# Input_channel.net
KiCad netlist of a schematic drawn in Altium Designer
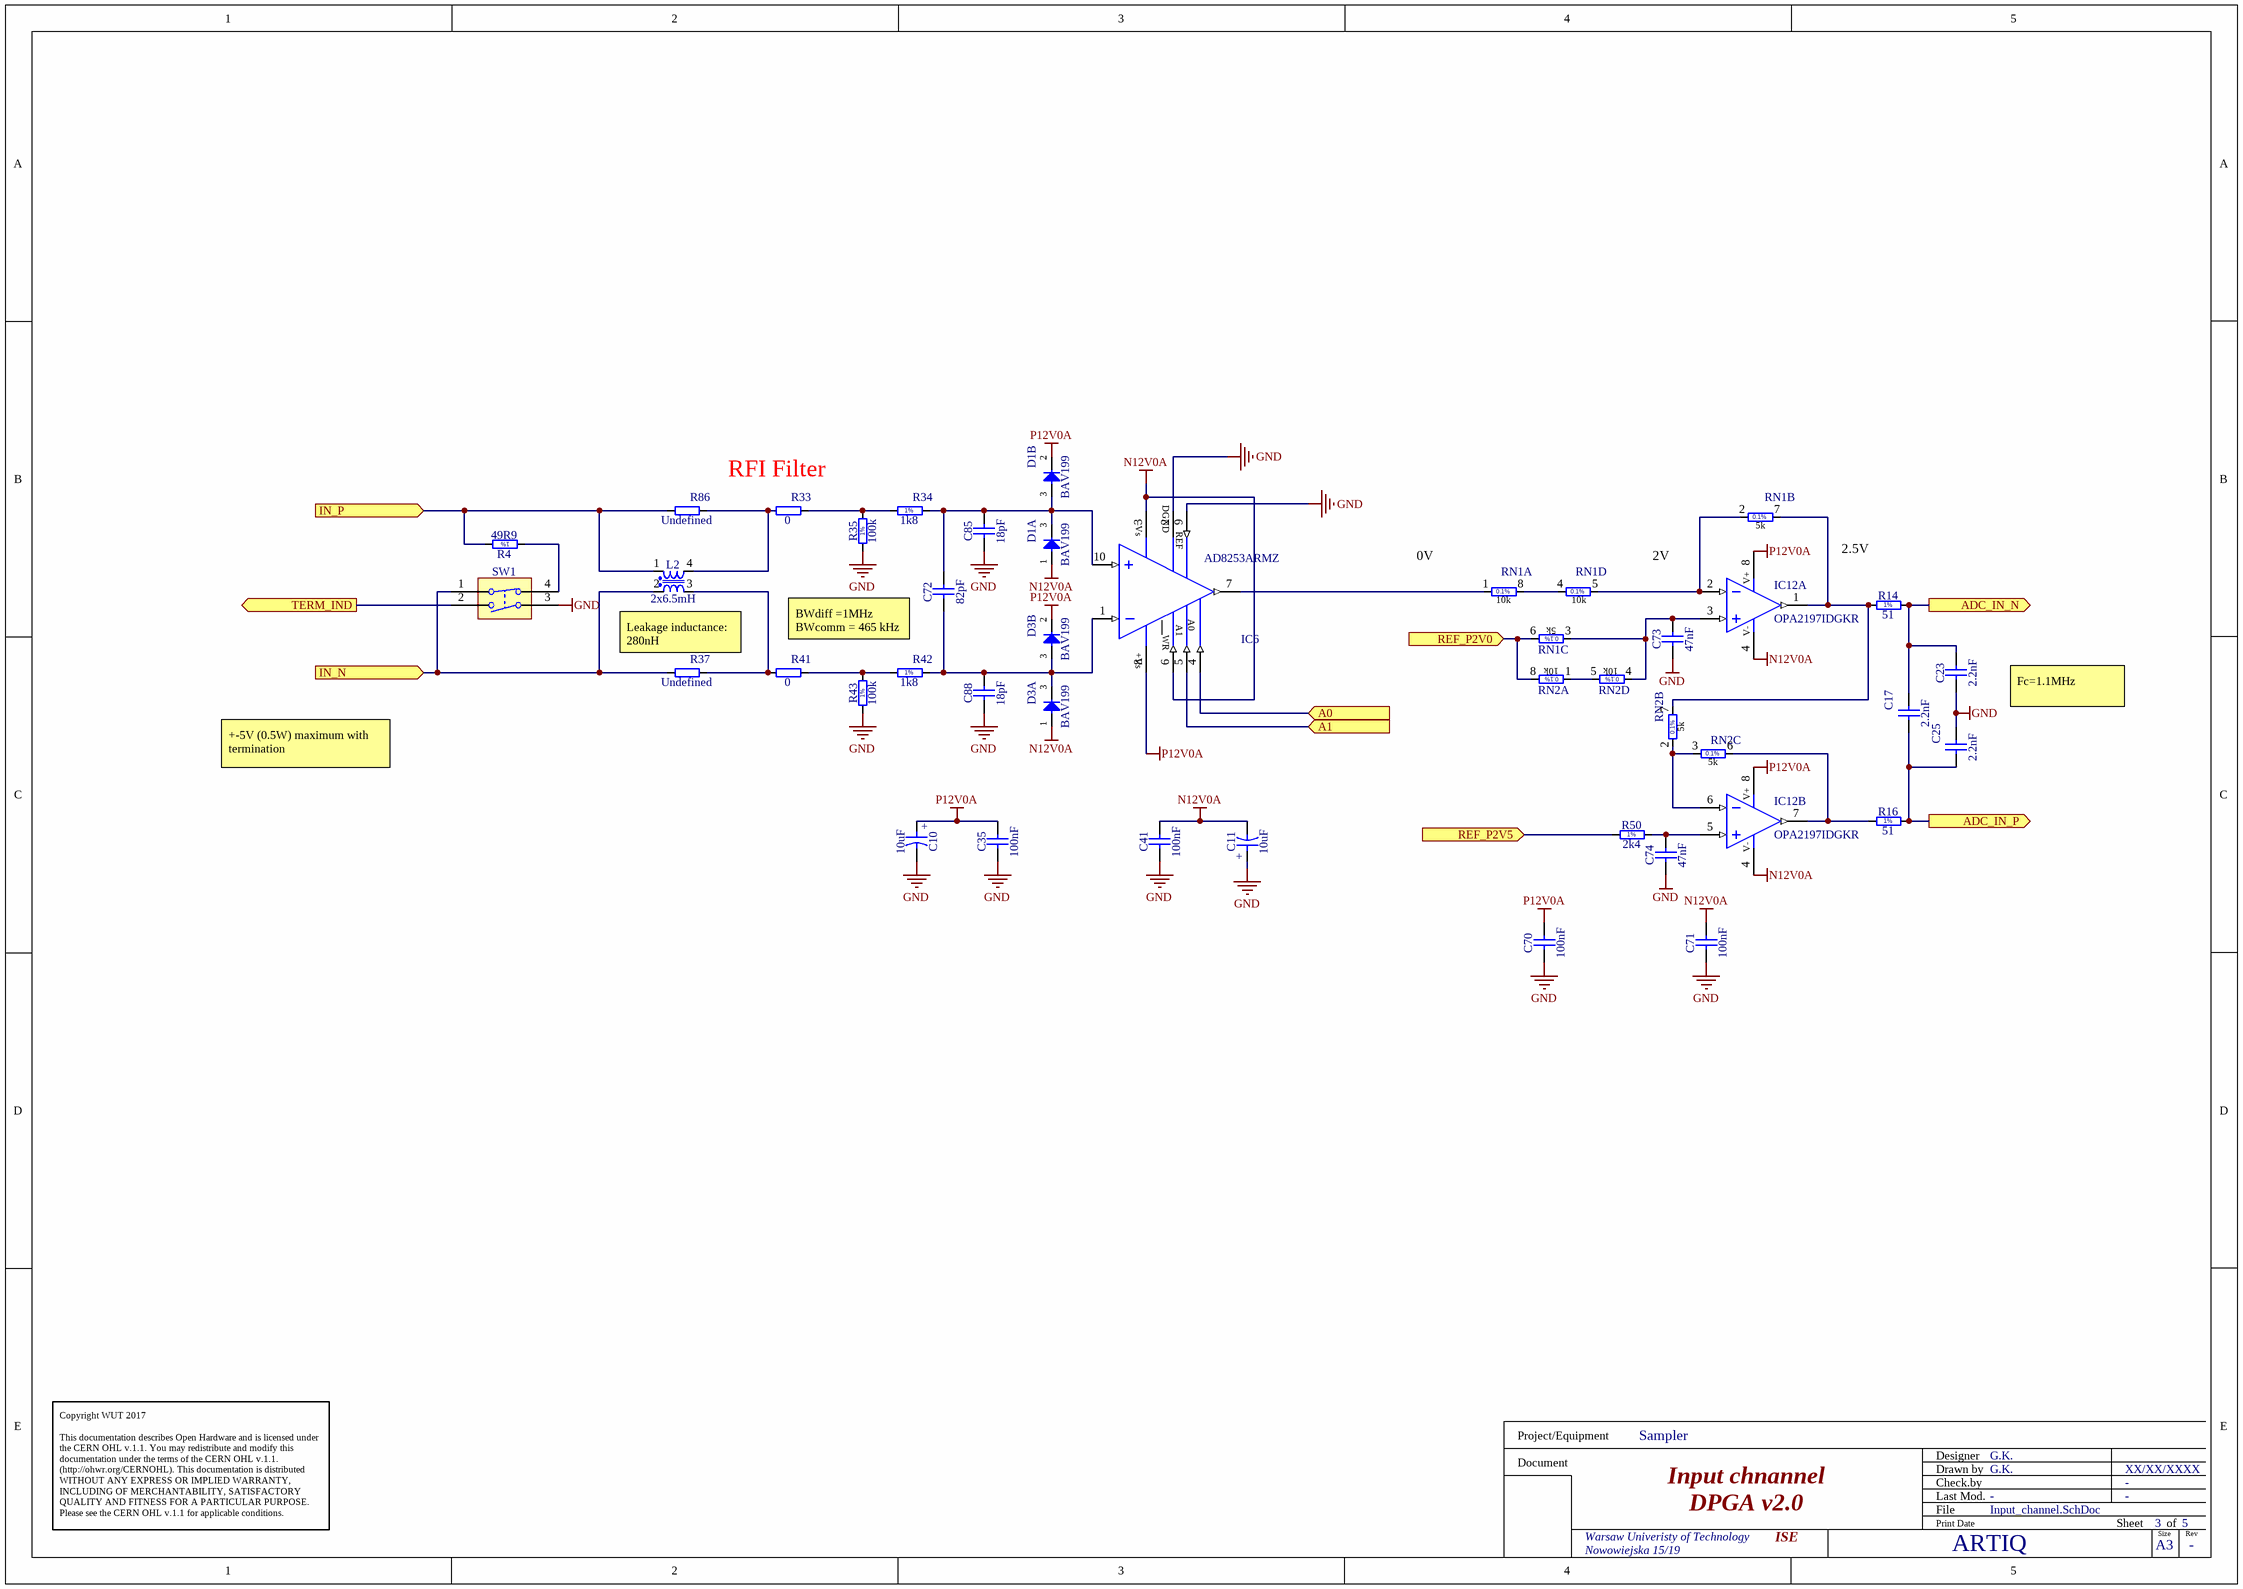
[diagram p0: Input_channel.SchDoc]

(export (version "E")
  (design (tool "Eeschema 10.0.6"))
  (components
    (comp (ref "C10")
      (value "10uF")
      (footprint "CAPMP3216X180N")
      (description "Polarised capacitor")
      (fields
        (field (name "PART NUMBER") "CTE3216-18_10UF_16V_20%_AVX_TCJ")
        (field (name "VOLTAGE") "16V")
        (field (name "AUTHOR") "CERN DEM JLC")
      )
      (libsource (lib "Capacitors") (part "Capacitor - polarized"))
    )
    (comp (ref "C11")
      (value "10uF")
      (footprint "CAPMP3216X180N")
      (description "Polarised capacitor")
      (fields
        (field (name "PART NUMBER") "CTE3216-18_10UF_16V_20%_AVX_TCJ")
        (field (name "VOLTAGE") "16V")
        (field (name "AUTHOR") "CERN DEM JLC")
      )
      (libsource (lib "Capacitors") (part "Capacitor - polarized"))
    )
    (comp (ref "C17")
      (value "2.2nF")
      (footprint "CAPC2013X100N")
      (description "Non-polarised capacitor")
      (fields
        (field (name "PART NUMBER") "CC0805_2.2NF_25V_1%_C0G")
        (field (name "VOLTAGE") "25V")
        (field (name "AUTHOR") "CERN DEM JLC")
      )
      (libsource (lib "Capacitors") (part "Capacitor - non polarized"))
    )
    (comp (ref "C23")
      (value "2.2nF")
      (footprint "CAPC2013X100N")
      (description "Non-polarised capacitor")
      (fields
        (field (name "PART NUMBER") "CC0805_2.2NF_25V_1%_C0G")
        (field (name "VOLTAGE") "25V")
        (field (name "AUTHOR") "CERN DEM JLC")
      )
      (libsource (lib "Capacitors") (part "Capacitor - non polarized"))
    )
    (comp (ref "C25")
      (value "2.2nF")
      (footprint "CAPC2013X100N")
      (description "Non-polarised capacitor")
      (fields
        (field (name "PART NUMBER") "CC0805_2.2NF_25V_1%_C0G")
        (field (name "VOLTAGE") "25V")
        (field (name "AUTHOR") "CERN DEM JLC")
      )
      (libsource (lib "Capacitors") (part "Capacitor - non polarized"))
    )
    (comp (ref "C35")
      (value "100nF")
      (footprint "CAPC1005X55N")
      (description "Non-polarised capacitor")
      (fields
        (field (name "PART NUMBER") "CC0402_100NF_16V_10%_X7R")
        (field (name "VOLTAGE") "16V")
        (field (name "AUTHOR") "CERN DEM JLC")
      )
      (libsource (lib "Capacitors") (part "Capacitor - non polarized"))
    )
    (comp (ref "C41")
      (value "100nF")
      (footprint "CAPC1005X55N")
      (description "Non-polarised capacitor")
      (fields
        (field (name "PART NUMBER") "CC0402_100NF_16V_10%_X7R")
        (field (name "VOLTAGE") "16V")
        (field (name "AUTHOR") "CERN DEM JLC")
      )
      (libsource (lib "Capacitors") (part "Capacitor - non polarized"))
    )
    (comp (ref "C70")
      (value "100nF")
      (footprint "CAPC1005X55N")
      (description "Non-polarised capacitor")
      (fields
        (field (name "PART NUMBER") "CC0402_100NF_16V_10%_X7R")
        (field (name "VOLTAGE") "16V")
        (field (name "AUTHOR") "CERN DEM JLC")
      )
      (libsource (lib "Capacitors") (part "Capacitor - non polarized"))
    )
    (comp (ref "C71")
      (value "100nF")
      (footprint "CAPC1005X55N")
      (description "Non-polarised capacitor")
      (fields
        (field (name "PART NUMBER") "CC0402_100NF_16V_10%_X7R")
        (field (name "VOLTAGE") "16V")
        (field (name "AUTHOR") "CERN DEM JLC")
      )
      (libsource (lib "Capacitors") (part "Capacitor - non polarized"))
    )
    (comp (ref "C72")
      (value "82pF")
      (footprint "CAPC2012X90N")
      (description "Non-polarised capacitor")
      (fields
        (field (name "PART NUMBER") "CC0805_82PF_100V_1%_NP0_AVX_08051A820FAT2A")
        (field (name "VOLTAGE") "100V")
        (field (name "AUTHOR") "CERN DEM WB")
      )
      (libsource (lib "Capacitors") (part "Capacitor - non polarized"))
    )
    (comp (ref "C73")
      (value "47nF")
      (footprint "CAPC2012X135N")
      (description "Non-polarised capacitor")
      (fields
        (field (name "PART NUMBER") "CC0805_47NF_25V_5%_C0G")
        (field (name "VOLTAGE") "25V")
        (field (name "AUTHOR") "CERN DEM JLC")
      )
      (libsource (lib "Capacitors") (part "Capacitor - non polarized"))
    )
    (comp (ref "C74")
      (value "47nF")
      (footprint "CAPC2012X135N")
      (description "Non-polarised capacitor")
      (fields
        (field (name "PART NUMBER") "CC0805_47NF_25V_5%_C0G")
        (field (name "VOLTAGE") "25V")
        (field (name "AUTHOR") "CERN DEM JLC")
      )
      (libsource (lib "Capacitors") (part "Capacitor - non polarized"))
    )
    (comp (ref "C85")
      (value "18pF")
      (footprint "CAPC1608X87N")
      (description "Non-polarised capacitor")
      (fields
        (field (name "PART NUMBER") "CC0603_18PF_50V_5%_NP0")
        (field (name "VOLTAGE") "50V")
        (field (name "AUTHOR") "CERN DEM JLC")
      )
      (libsource (lib "Capacitors") (part "Capacitor - non polarized"))
    )
    (comp (ref "C88")
      (value "18pF")
      (footprint "CAPC1608X87N")
      (description "Non-polarised capacitor")
      (fields
        (field (name "PART NUMBER") "CC0603_18PF_50V_5%_NP0")
        (field (name "VOLTAGE") "50V")
        (field (name "AUTHOR") "CERN DEM JLC")
      )
      (libsource (lib "Capacitors") (part "Capacitor - non polarized"))
    )
    (comp (ref "D1")
      (value "BAV199")
      (footprint "SOT95P240X110-3N")
      (description "Serial Diode")
      (fields
        (field (name "VOLTAGE") "75V")
        (field (name "POWER") "250mW")
        (field (name "AUTHOR") "CERN DEM JMW")
      )
      (libsource (lib "ICs And Semiconductors") (part "Diode x2 A1C3_A3C2"))
    )
    (comp (ref "D3")
      (value "BAV199")
      (footprint "SOT95P240X110-3N")
      (description "Serial Diode")
      (fields
        (field (name "VOLTAGE") "75V")
        (field (name "POWER") "250mW")
        (field (name "AUTHOR") "CERN DEM JMW")
      )
      (libsource (lib "ICs And Semiconductors") (part "Diode x2 A1C3_A3C2"))
    )
    (comp (ref "IC6")
      (value "AD8253ARMZ")
      (footprint "SOP50P490X110-10N")
      (description "10MHz, 20V/us, G= 1, 10, 100, 1000 iCMOS Programmable Gain Instrumentation Amplifier")
      (fields (field (name "MANUFACTURER") "ANALOG DEVICES") (field (name "AUTHOR") "CERN DEM JLC"))
      (libsource (lib "ICs And Semiconductors") (part "AD8253"))
    )
    (comp (ref "IC12")
      (value "OPA2197IDGKR")
      (footprint "SOP65P490X110-8N")
      (description "36-V, Precision, Rail-to-Rail Input Output, Low Offset Voltage Op Amp 8-VSSOP")
      (fields (field (name "MANUFACTURER") "TEXAS INSTRUMENTS") (field (name "AUTHOR") "GK"))
      (libsource (lib "LIBRARY_SCH") (part "OA_OPA2197IDGKR"))
    )
    (comp (ref "L2")
      (value "2x6.5mH")
      (footprint "IND_WURTH_WE-SL2")
      (description "Inductor Common Mode")
      (fields
        (field (name "PART NUMBER") "IND_6.5MH_50%_WURTH_WE-SL2-744229")
        (field (name "POWER") "400mA")
        (field (name "AUTHOR") "CERN DEM JLC")
      )
      (libsource (lib "Inductors & Transformers") (part "Inductor Common Mode 1Dot-4 2Dot-3"))
    )
    (comp (ref "R4")
      (value "49R9")
      (footprint "RESC6331X70N")
      (description "Resistor - 1%")
      (fields
        (field (name "PART NUMBER") "R2512_49R9_1%_1W_100PPM_VISHAY_CRCW")
        (field (name "POWER") "1W")
        (field (name "AUTHOR") "CERN DEM JLC")
      )
      (libsource (lib "Resistors") (part "Resistor - 1%"))
    )
    (comp (ref "R14")
      (value "51")
      (footprint "RESC1005X40N")
      (description "Resistor - 1%")
      (fields
        (field (name "PART NUMBER") "R0402_51R_1%_0.0625W_100PPM")
        (field (name "POWER") "0.0625W")
        (field (name "AUTHOR") "CERN DEM JLC")
      )
      (libsource (lib "Resistors") (part "Resistor - 1%"))
    )
    (comp (ref "R16")
      (value "51")
      (footprint "RESC1005X40N")
      (description "Resistor - 1%")
      (fields
        (field (name "PART NUMBER") "R0402_51R_1%_0.0625W_100PPM")
        (field (name "POWER") "0.0625W")
        (field (name "AUTHOR") "CERN DEM JLC")
      )
      (libsource (lib "Resistors") (part "Resistor - 1%"))
    )
    (comp (ref "R33")
      (value "0")
      (footprint "RESC1608X55N")
      (description "Resistor")
      (fields
        (field (name "PART NUMBER") "R0603_0R_JUMPER")
        (field (name "MANUFACTURER") "GENERIC")
        (field (name "AUTHOR") "CERN DEM JLC")
      )
      (libsource (lib "Resistors") (part "Resistor"))
    )
    (comp (ref "R34")
      (value "1k8")
      (footprint "RESC1608X55N")
      (description "Resistor - 1%")
      (fields
        (field (name "PART NUMBER") "R0603_1K8_1%_0.1W_100PPM")
        (field (name "POWER") "0.1W")
        (field (name "AUTHOR") "CERN DEM JLC")
      )
      (libsource (lib "Resistors") (part "Resistor - 1%"))
    )
    (comp (ref "R35")
      (value "100k")
      (footprint "RESC1608X55N")
      (description "Resistor - 1%")
      (fields
        (field (name "PART NUMBER") "R0603_100K_1%_0.1W_100PPM")
        (field (name "POWER") "0.1W")
        (field (name "AUTHOR") "CERN DEM JLC")
      )
      (libsource (lib "Resistors") (part "Resistor - 1%"))
    )
    (comp (ref "R37")
      (value "Undefined")
      (footprint "RESC1608X55N")
      (description "Resistor")
      (fields (field (name "PART NUMBER") "R0603_NO-VALUE") (field (name "AUTHOR") "CERN DEM JLC"))
      (libsource (lib "Resistors") (part "Resistor"))
    )
    (comp (ref "R41")
      (value "0")
      (footprint "RESC1608X55N")
      (description "Resistor")
      (fields
        (field (name "PART NUMBER") "R0603_0R_JUMPER")
        (field (name "MANUFACTURER") "GENERIC")
        (field (name "AUTHOR") "CERN DEM JLC")
      )
      (libsource (lib "Resistors") (part "Resistor"))
    )
    (comp (ref "R42")
      (value "1k8")
      (footprint "RESC1608X55N")
      (description "Resistor - 1%")
      (fields
        (field (name "PART NUMBER") "R0603_1K8_1%_0.1W_100PPM")
        (field (name "POWER") "0.1W")
        (field (name "AUTHOR") "CERN DEM JLC")
      )
      (libsource (lib "Resistors") (part "Resistor - 1%"))
    )
    (comp (ref "R43")
      (value "100k")
      (footprint "RESC1608X55N")
      (description "Resistor - 1%")
      (fields
        (field (name "PART NUMBER") "R0603_100K_1%_0.1W_100PPM")
        (field (name "POWER") "0.1W")
        (field (name "AUTHOR") "CERN DEM JLC")
      )
      (libsource (lib "Resistors") (part "Resistor - 1%"))
    )
    (comp (ref "R50")
      (value "2k4")
      (footprint "RESC1005X40N")
      (description "Resistor - 1%")
      (fields
        (field (name "PART NUMBER") "R0402_2K4_1%_0.0625W_100PPM")
        (field (name "POWER") "0.0625W")
        (field (name "AUTHOR") "CERN DEM JLC")
      )
      (libsource (lib "Resistors") (part "Resistor - 1%"))
    )
    (comp (ref "R86")
      (value "Undefined")
      (footprint "RESC1608X55N")
      (description "Resistor")
      (fields (field (name "PART NUMBER") "R0603_NO-VALUE") (field (name "AUTHOR") "CERN DEM JLC"))
      (libsource (lib "Resistors") (part "Resistor"))
    )
    (comp (ref "RN1")
      (value "10k 5K 5K 10K")
      (footprint "SOIC127P600X175-8N")
      (description "DIL8 Resistor Network 4 Resistors 10k-5k-5k-10k 0.1%")
      (fields
        (field (name "PART NUMBER") "RN_10K_5K_VISHAY_AORN2-1AT3")
        (field (name "POWER") "4x0.1W")
        (field (name "AUTHOR") "CERN DEM JLC")
      )
      (libsource (lib "Resistors") (part "RN DIL8_4xR_10k-5k-5k-10k_0.1%"))
    )
    (comp (ref "RN2")
      (value "10k 5K 5K 10K")
      (footprint "SOIC127P600X175-8N")
      (description "DIL8 Resistor Network 4 Resistors 10k-5k-5k-10k 0.1%")
      (fields
        (field (name "PART NUMBER") "RN_10K_5K_VISHAY_AORN2-1AT3")
        (field (name "POWER") "4x0.1W")
        (field (name "AUTHOR") "CERN DEM JLC")
      )
      (libsource (lib "Resistors") (part "RN DIL8_4xR_10k-5k-5k-10k_0.1%"))
    )
    (comp (ref "SW1")
      (value "Switch")
      (footprint "SW_CTS_204-121ST")
      (description "2x SPST DIP Switch 1NO + 1NF")
      (fields
        (field (name "PART NUMBER") "SW_CTS_204-121ST")
        (field (name "MANUFACTURER") "CTS")
        (field (name "AUTHOR") "CERN DEM JLC")
      )
      (libsource (lib "Eletro-mechanical") (part "SW_CTS_204-121ST"))
    )
  )
  (nets
    (net (code "1") (name "/A0") (class "Default")
      (node (ref "IC6") (pin "4") (pinfunction "A0_4") (pintype "input"))
    )
    (net (code "2") (name "/A1") (class "Default")
      (node (ref "IC6") (pin "5") (pinfunction "A1_5") (pintype "input"))
    )
    (net (code "3") (name "/ADC_IN_N") (class "Default")
      (node (ref "C17") (pin "2") (pinfunction "2_2") (pintype "passive"))
      (node (ref "C23") (pin "2") (pinfunction "2_2") (pintype "passive"))
      (node (ref "R14") (pin "2") (pinfunction "2_2") (pintype "passive"))
    )
    (net (code "4") (name "/ADC_IN_P") (class "Default")
      (node (ref "C17") (pin "1") (pinfunction "1_1") (pintype "passive"))
      (node (ref "C25") (pin "1") (pinfunction "1_1") (pintype "passive"))
      (node (ref "R16") (pin "2") (pinfunction "2_2") (pintype "passive"))
    )
    (net (code "5") (name "/IN_N") (class "Default")
      (node (ref "L2") (pin "2") (pinfunction "2_2") (pintype "passive"))
      (node (ref "R37") (pin "1") (pinfunction "1_1") (pintype "passive"))
      (node (ref "SW1") (pin "1") (pinfunction "1_1") (pintype "passive"))
    )
    (net (code "6") (name "/IN_P") (class "Default")
      (node (ref "L2") (pin "1") (pinfunction "1_1") (pintype "passive"))
      (node (ref "R4") (pin "2") (pinfunction "2_2") (pintype "passive"))
      (node (ref "R86") (pin "1") (pinfunction "1_1") (pintype "passive"))
    )
    (net (code "7") (name "/REF_P2V0") (class "Default")
      (node (ref "RN1") (pin "6") (pinfunction "6_6") (pintype "passive"))
      (node (ref "RN2") (pin "8") (pinfunction "8_8") (pintype "passive"))
    )
    (net (code "8") (name "/REF_P2V5") (class "Default")
      (node (ref "R50") (pin "1") (pinfunction "1_1") (pintype "passive"))
    )
    (net (code "9") (name "/TERM_IND") (class "Default")
      (node (ref "SW1") (pin "2") (pinfunction "2_2") (pintype "passive"))
    )
    (net (code "10") (name "GND") (class "Default")
      (node (ref "C10") (pin "2") (pinfunction "2_2") (pintype "passive"))
      (node (ref "C11") (pin "1") (pinfunction "1_1") (pintype "passive"))
      (node (ref "C23") (pin "1") (pinfunction "1_1") (pintype "passive"))
      (node (ref "C25") (pin "2") (pinfunction "2_2") (pintype "passive"))
      (node (ref "C35") (pin "1") (pinfunction "1_1") (pintype "passive"))
      (node (ref "C41") (pin "1") (pinfunction "1_1") (pintype "passive"))
      (node (ref "C70") (pin "1") (pinfunction "1_1") (pintype "passive"))
      (node (ref "C71") (pin "1") (pinfunction "1_1") (pintype "passive"))
      (node (ref "C73") (pin "1") (pinfunction "1_1") (pintype "passive"))
      (node (ref "C74") (pin "1") (pinfunction "1_1") (pintype "passive"))
      (node (ref "C85") (pin "1") (pinfunction "1_1") (pintype "passive"))
      (node (ref "C88") (pin "1") (pinfunction "1_1") (pintype "passive"))
      (node (ref "IC6") (pin "2") (pinfunction "DGND_2") (pintype "power_in"))
      (node (ref "IC6") (pin "9") (pinfunction "REF_9") (pintype "input"))
      (node (ref "R35") (pin "1") (pinfunction "1_1") (pintype "passive"))
      (node (ref "R43") (pin "1") (pinfunction "1_1") (pintype "passive"))
      (node (ref "SW1") (pin "3") (pinfunction "3_3") (pintype "passive"))
    )
    (net (code "11") (name "N12V0A") (class "Default")
      (node (ref "C11") (pin "2") (pinfunction "2_2") (pintype "passive"))
      (node (ref "C41") (pin "2") (pinfunction "2_2") (pintype "passive"))
      (node (ref "C71") (pin "2") (pinfunction "2_2") (pintype "passive"))
      (node (ref "D1") (pin "1") (pinfunction "A_1") (pintype "passive"))
      (node (ref "D3") (pin "1") (pinfunction "A_1") (pintype "passive"))
      (node (ref "IC12") (pin "4") (pinfunction "V-_4") (pintype "power_in"))
      (node (ref "IC6") (pin "3") (pinfunction "-VS_3") (pintype "power_in"))
      (node (ref "IC6") (pin "6") (pinfunction "~{WR}_6") (pintype "input"))
    )
    (net (code "12") (name "Net-(D1A-COMAC)") (class "Default")
      (node (ref "C72") (pin "2") (pinfunction "2_2") (pintype "passive"))
      (node (ref "C85") (pin "2") (pinfunction "2_2") (pintype "passive"))
      (node (ref "D1") (pin "3") (pinfunction "COMAC_3") (pintype "passive"))
      (node (ref "IC6") (pin "10") (pinfunction "+IN_10") (pintype "input"))
      (node (ref "R34") (pin "2") (pinfunction "2_2") (pintype "passive"))
    )
    (net (code "13") (name "Net-(D3A-COMAC)") (class "Default")
      (node (ref "C72") (pin "1") (pinfunction "1_1") (pintype "passive"))
      (node (ref "C88") (pin "2") (pinfunction "2_2") (pintype "passive"))
      (node (ref "D3") (pin "3") (pinfunction "COMAC_3") (pintype "passive"))
      (node (ref "IC6") (pin "1") (pinfunction "-IN_1") (pintype "input"))
      (node (ref "R42") (pin "2") (pinfunction "2_2") (pintype "passive"))
    )
    (net (code "14") (name "Net-(IC6-OUT)") (class "Default")
      (node (ref "IC6") (pin "7") (pinfunction "OUT_7") (pintype "output"))
      (node (ref "RN1") (pin "1") (pinfunction "1_1") (pintype "passive"))
    )
    (net (code "15") (name "Net-(IC12A-IN+)") (class "Default")
      (node (ref "C73") (pin "2") (pinfunction "2_2") (pintype "passive"))
      (node (ref "IC12") (pin "3") (pinfunction "IN+_3") (pintype "input"))
      (node (ref "RN1") (pin "3") (pinfunction "3_3") (pintype "passive"))
      (node (ref "RN2") (pin "4") (pinfunction "4_4") (pintype "passive"))
    )
    (net (code "16") (name "Net-(IC12A-IN-)") (class "Default")
      (node (ref "IC12") (pin "2") (pinfunction "IN-_2") (pintype "input"))
      (node (ref "RN1") (pin "2") (pinfunction "2_2") (pintype "passive"))
      (node (ref "RN1") (pin "5") (pinfunction "5_5") (pintype "passive"))
    )
    (net (code "17") (name "Net-(IC12A-OUT)") (class "Default")
      (node (ref "IC12") (pin "1") (pinfunction "OUT_1") (pintype "output"))
      (node (ref "R14") (pin "1") (pinfunction "1_1") (pintype "passive"))
      (node (ref "RN1") (pin "7") (pinfunction "7_7") (pintype "passive"))
      (node (ref "RN2") (pin "7") (pinfunction "7_7") (pintype "passive"))
    )
    (net (code "18") (name "Net-(IC12B-IN+)") (class "Default")
      (node (ref "C74") (pin "2") (pinfunction "2_2") (pintype "passive"))
      (node (ref "IC12") (pin "5") (pinfunction "IN+_5") (pintype "input"))
      (node (ref "R50") (pin "2") (pinfunction "2_2") (pintype "passive"))
    )
    (net (code "19") (name "Net-(IC12B-IN-)") (class "Default")
      (node (ref "IC12") (pin "6") (pinfunction "IN-_6") (pintype "input"))
      (node (ref "RN2") (pin "2") (pinfunction "2_2") (pintype "passive"))
      (node (ref "RN2") (pin "3") (pinfunction "3_3") (pintype "passive"))
    )
    (net (code "20") (name "Net-(IC12B-OUT)") (class "Default")
      (node (ref "IC12") (pin "7") (pinfunction "OUT_7") (pintype "output"))
      (node (ref "R16") (pin "1") (pinfunction "1_1") (pintype "passive"))
      (node (ref "RN2") (pin "6") (pinfunction "6_6") (pintype "passive"))
    )
    (net (code "21") (name "Net-(L2-Pad3)") (class "Default")
      (node (ref "L2") (pin "3") (pinfunction "3_3") (pintype "passive"))
      (node (ref "R37") (pin "2") (pinfunction "2_2") (pintype "passive"))
      (node (ref "R41") (pin "1") (pinfunction "1_1") (pintype "passive"))
    )
    (net (code "22") (name "Net-(L2-Pad4)") (class "Default")
      (node (ref "L2") (pin "4") (pinfunction "4_4") (pintype "passive"))
      (node (ref "R33") (pin "1") (pinfunction "1_1") (pintype "passive"))
      (node (ref "R86") (pin "2") (pinfunction "2_2") (pintype "passive"))
    )
    (net (code "23") (name "Net-(R4-Pad1)") (class "Default")
      (node (ref "R4") (pin "1") (pinfunction "1_1") (pintype "passive"))
      (node (ref "SW1") (pin "4") (pinfunction "4_4") (pintype "passive"))
    )
    (net (code "24") (name "Net-(R33-Pad2)") (class "Default")
      (node (ref "R33") (pin "2") (pinfunction "2_2") (pintype "passive"))
      (node (ref "R34") (pin "1") (pinfunction "1_1") (pintype "passive"))
      (node (ref "R35") (pin "2") (pinfunction "2_2") (pintype "passive"))
    )
    (net (code "25") (name "Net-(R41-Pad2)") (class "Default")
      (node (ref "R41") (pin "2") (pinfunction "2_2") (pintype "passive"))
      (node (ref "R42") (pin "1") (pinfunction "1_1") (pintype "passive"))
      (node (ref "R43") (pin "2") (pinfunction "2_2") (pintype "passive"))
    )
    (net (code "26") (name "Net-(RN1-Pad4)") (class "Default")
      (node (ref "RN1") (pin "4") (pinfunction "4_4") (pintype "passive"))
      (node (ref "RN1") (pin "8") (pinfunction "8_8") (pintype "passive"))
    )
    (net (code "27") (name "Net-(RN2-Pad1)") (class "Default")
      (node (ref "RN2") (pin "1") (pinfunction "1_1") (pintype "passive"))
      (node (ref "RN2") (pin "5") (pinfunction "5_5") (pintype "passive"))
    )
    (net (code "28") (name "P12V0A") (class "Default")
      (node (ref "C10") (pin "1") (pinfunction "1_1") (pintype "passive"))
      (node (ref "C35") (pin "2") (pinfunction "2_2") (pintype "passive"))
      (node (ref "C70") (pin "2") (pinfunction "2_2") (pintype "passive"))
      (node (ref "D1") (pin "2") (pinfunction "C_2") (pintype "passive"))
      (node (ref "D3") (pin "2") (pinfunction "C_2") (pintype "passive"))
      (node (ref "IC12") (pin "8") (pinfunction "V+_8") (pintype "power_in"))
      (node (ref "IC6") (pin "8") (pinfunction "+VS_8") (pintype "power_in"))
    )
  )
)
